# motor4.net
KiCad netlist of a schematic drawn in EAGLE
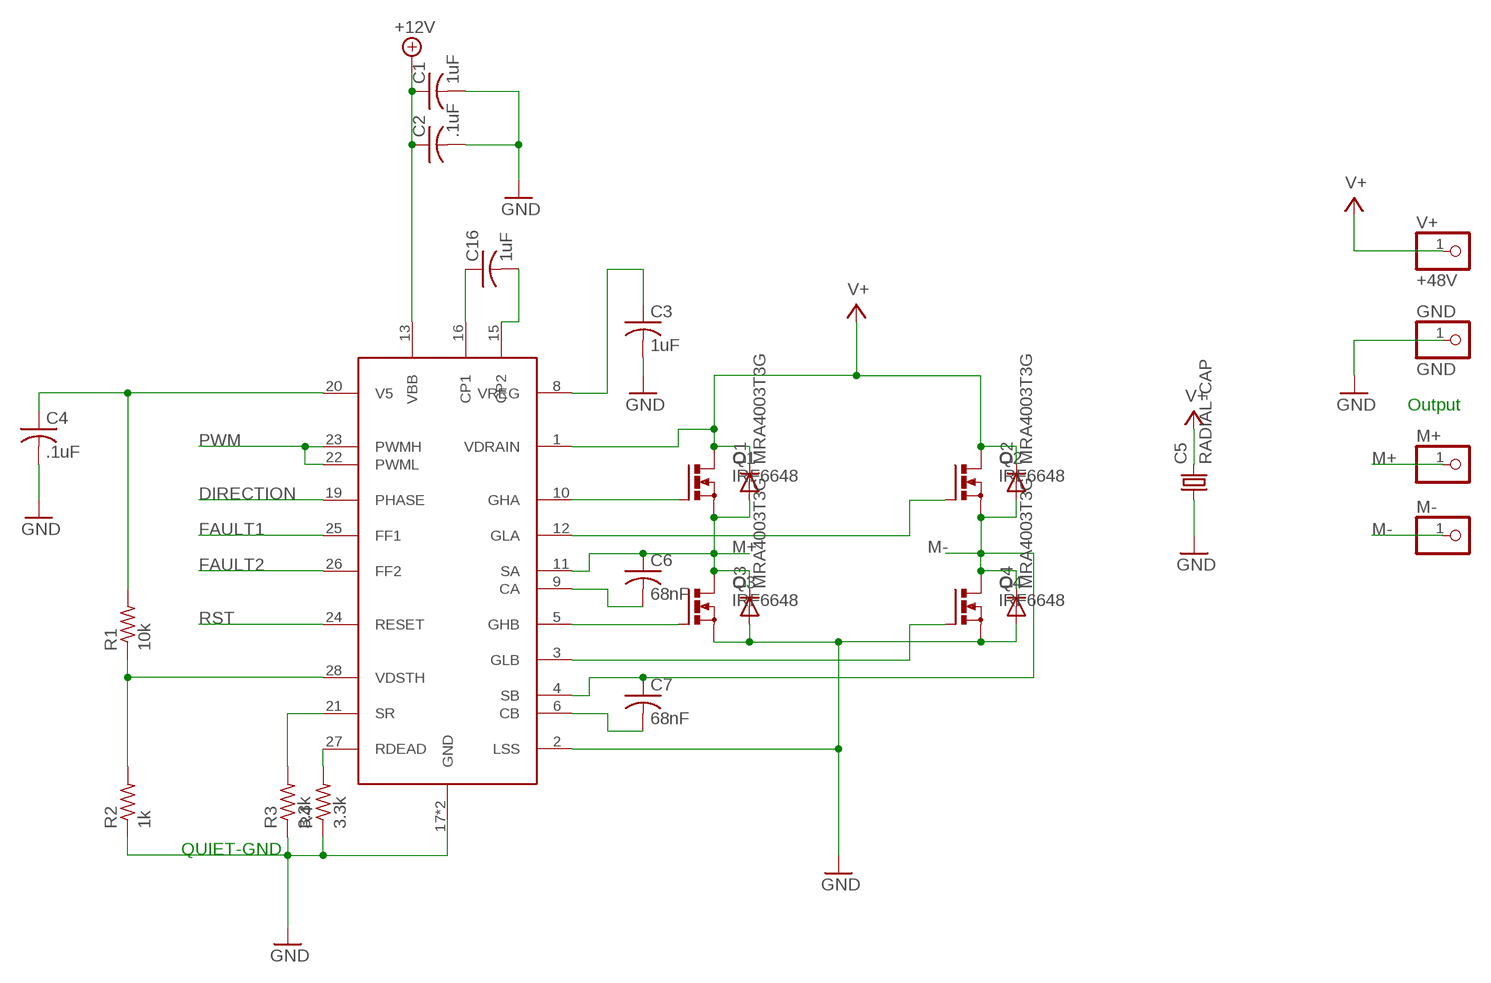
[diagram p0: schematic, sheet 1]
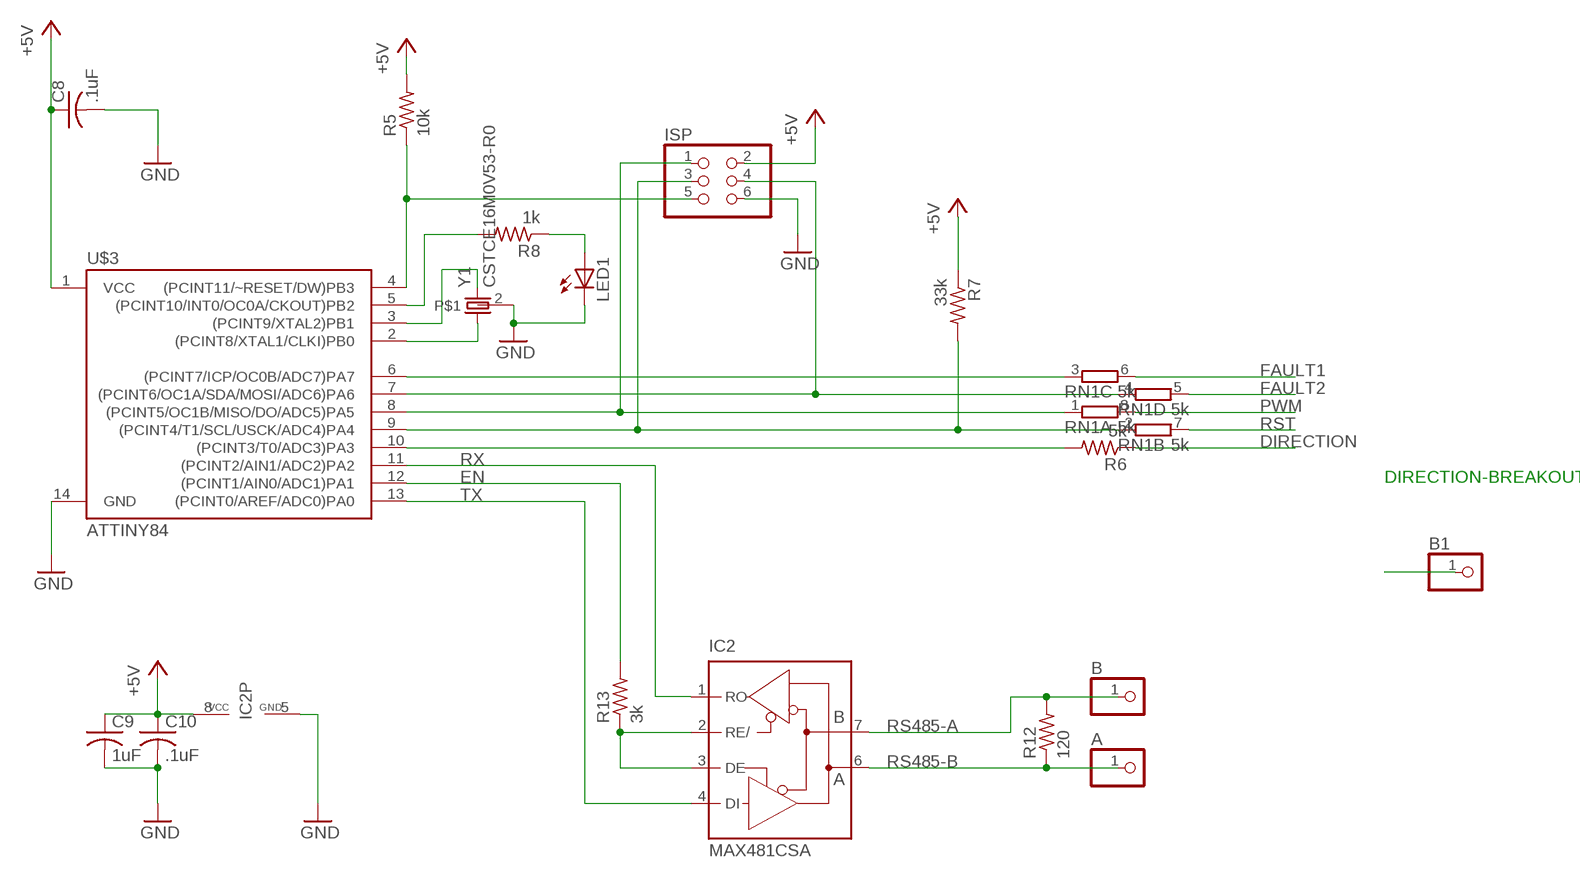
[diagram p1: schematic, sheet 2]
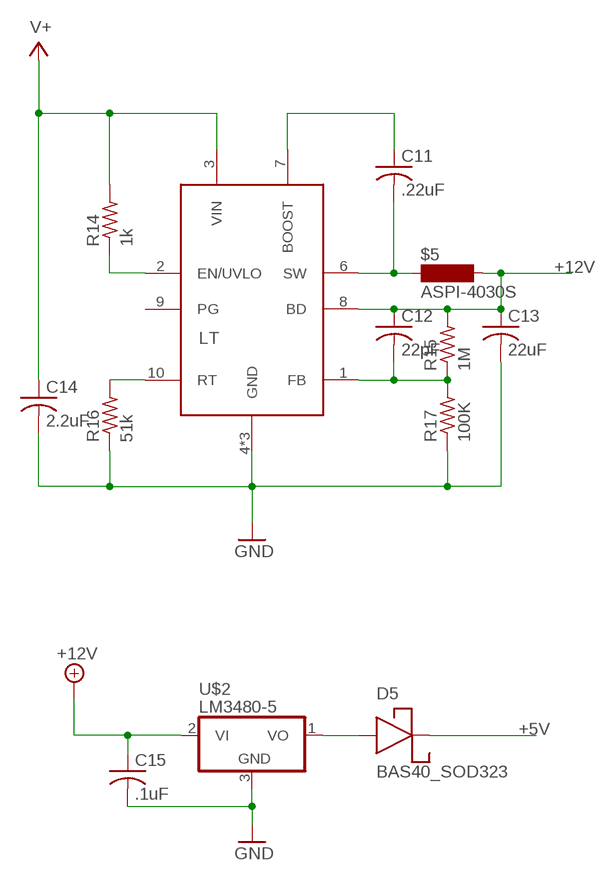
[diagram p2: schematic, sheet 3]

(export (version "E")
  (design (tool "Eeschema 10.0.6"))
  (components
    (comp (ref "$5")
      (value "ASPI-4030S")
      (footprint "eagle-import:ASPI-4030S")
      (libsource (lib "eagle-import") (part "ASPI-4030S"))
    )
    (comp (ref "C11")
      (value ".22uF")
      (footprint "eagle-import:C0603")
      (libsource (lib "eagle-import") (part "C-USC0603"))
    )
    (comp (ref "C12")
      (value "22pF")
      (footprint "eagle-import:C0603")
      (libsource (lib "eagle-import") (part "C-USC0603"))
    )
    (comp (ref "C13")
      (value "22uF")
      (footprint "eagle-import:C0805")
      (libsource (lib "eagle-import") (part "C-USC0805"))
    )
    (comp (ref "C14")
      (value "2.2uF")
      (footprint "eagle-import:C0603")
      (libsource (lib "eagle-import") (part "C-USC0603"))
    )
    (comp (ref "C15")
      (value ".1uF")
      (footprint "eagle-import:C0603")
      (libsource (lib "eagle-import") (part "C-USC0603"))
    )
    (comp (ref "D5")
      (value "BAS40_SOD323")
      (footprint "eagle-import:SOD323")
      (libsource (lib "eagle-import") (part "BAS40_SOD323"))
    )
    (comp (ref "LT")
      (value "LT3990")
      (footprint "eagle-import:DFN10-3X3")
      (libsource (lib "eagle-import") (part "LT3990"))
    )
    (comp (ref "R14")
      (value "1k")
      (footprint "eagle-import:R0603")
      (libsource (lib "eagle-import") (part "R-US_R0603"))
    )
    (comp (ref "R15")
      (value "1M")
      (footprint "eagle-import:R0603")
      (libsource (lib "eagle-import") (part "R-US_R0603"))
    )
    (comp (ref "R16")
      (value "51k")
      (footprint "eagle-import:R0603")
      (libsource (lib "eagle-import") (part "R-US_R0603"))
    )
    (comp (ref "R17")
      (value "100K")
      (footprint "eagle-import:R0603")
      (libsource (lib "eagle-import") (part "R-US_R0603"))
    )
    (comp (ref "U$2")
      (value "LM3480-5")
      (footprint "eagle-import:SOT23")
      (libsource (lib "eagle-import") (part "LM3480-5"))
    )
    (comp (ref "A")
      (value "PINHD-1X1")
      (footprint "eagle-import:1X01")
      (libsource (lib "eagle-import") (part "PINHD-1X1"))
    )
    (comp (ref "B")
      (value "PINHD-1X1")
      (footprint "eagle-import:1X01")
      (libsource (lib "eagle-import") (part "PINHD-1X1"))
    )
    (comp (ref "B1")
      (value "PINHD-1X1")
      (footprint "eagle-import:1X01")
      (libsource (lib "eagle-import") (part "PINHD-1X1"))
    )
    (comp (ref "C8")
      (value ".1uF")
      (footprint "eagle-import:C0603")
      (libsource (lib "eagle-import") (part "C-USC0603"))
    )
    (comp (ref "C9")
      (value "1uF")
      (footprint "eagle-import:C0603")
      (libsource (lib "eagle-import") (part "C-USC0603"))
    )
    (comp (ref "C10")
      (value ".1uF")
      (footprint "eagle-import:C0603")
      (libsource (lib "eagle-import") (part "C-USC0603"))
    )
    (comp (ref "IC2")
      (value "MAX481CSA")
      (footprint "eagle-import:SO08")
      (fields (field (name "MF") "MAXIM"))
      (libsource (lib "eagle-import") (part "MAX481CSA"))
    )
    (comp (ref "ISP")
      (value "PINHD-2X3")
      (footprint "eagle-import:2X03")
      (libsource (lib "eagle-import") (part "PINHD-2X3"))
    )
    (comp (ref "LED1")
      (value "LEDCHIPLED_0603")
      (footprint "eagle-import:CHIPLED_0603")
      (libsource (lib "eagle-import") (part "LEDCHIPLED_0603"))
    )
    (comp (ref "R5")
      (value "10k")
      (footprint "eagle-import:R0603")
      (libsource (lib "eagle-import") (part "R-US_R0603"))
    )
    (comp (ref "R6")
      (value "5k")
      (footprint "eagle-import:R0603")
      (libsource (lib "eagle-import") (part "R-US_R0603"))
    )
    (comp (ref "R7")
      (value "33k")
      (footprint "eagle-import:R0603")
      (libsource (lib "eagle-import") (part "R-US_R0603"))
    )
    (comp (ref "R8")
      (value "1k")
      (footprint "eagle-import:R0603")
      (libsource (lib "eagle-import") (part "R-US_R0603"))
    )
    (comp (ref "R12")
      (value "120")
      (footprint "eagle-import:R0603")
      (libsource (lib "eagle-import") (part "R-US_R0603"))
    )
    (comp (ref "R13")
      (value "3k")
      (footprint "eagle-import:R0603")
      (libsource (lib "eagle-import") (part "R-US_R0603"))
    )
    (comp (ref "RN1")
      (value "5k")
      (footprint "eagle-import:EXB38V")
      (libsource (lib "eagle-import") (part "4R-NEXB38V"))
    )
    (comp (ref "U$3")
      (value "ATTINY84")
      (footprint "eagle-import:SO14")
      (libsource (lib "eagle-import") (part "ATTINY84"))
    )
    (comp (ref "Y1")
      (value "CSTCE16M0V53-R0")
      (footprint "eagle-import:MYSMD2_RESONATOR")
      (libsource (lib "eagle-import") (part "CSTCE16M0V53-R0"))
    )
    (comp (ref "ALLGR")
      (value "ALLEGRO-A3921")
      (footprint "eagle-import:TSSOP28")
      (libsource (lib "eagle-import") (part "ALLEGRO-A3921"))
    )
    (comp (ref "C1")
      (value "1uF")
      (footprint "eagle-import:C0603")
      (libsource (lib "eagle-import") (part "C-USC0603"))
    )
    (comp (ref "C2")
      (value ".1uF")
      (footprint "eagle-import:C0603")
      (libsource (lib "eagle-import") (part "C-USC0603"))
    )
    (comp (ref "C3")
      (value "1uF")
      (footprint "eagle-import:C0603")
      (libsource (lib "eagle-import") (part "C-USC0603"))
    )
    (comp (ref "C4")
      (value ".1uF")
      (footprint "eagle-import:C0603")
      (libsource (lib "eagle-import") (part "C-USC0603"))
    )
    (comp (ref "C5")
      (value "RADIAL-CAP")
      (footprint "eagle-import:RADIAL-CAP")
      (libsource (lib "eagle-import") (part "RADIAL-CAP"))
    )
    (comp (ref "C6")
      (value "68nF")
      (footprint "eagle-import:C0603")
      (libsource (lib "eagle-import") (part "C-USC0603"))
    )
    (comp (ref "C7")
      (value "68nF")
      (footprint "eagle-import:C0603")
      (libsource (lib "eagle-import") (part "C-USC0603"))
    )
    (comp (ref "C16")
      (value "1uF")
      (footprint "eagle-import:C0603")
      (libsource (lib "eagle-import") (part "C-USC0603"))
    )
    (comp (ref "D1")
      (value "MRA4003T3G")
      (footprint "eagle-import:SMA")
      (libsource (lib "eagle-import") (part "MRA4003T3G"))
    )
    (comp (ref "D2")
      (value "MRA4003T3G")
      (footprint "eagle-import:SMA")
      (libsource (lib "eagle-import") (part "MRA4003T3G"))
    )
    (comp (ref "D3")
      (value "MRA4003T3G")
      (footprint "eagle-import:SMA")
      (libsource (lib "eagle-import") (part "MRA4003T3G"))
    )
    (comp (ref "D4")
      (value "MRA4003T3G")
      (footprint "eagle-import:SMA")
      (libsource (lib "eagle-import") (part "MRA4003T3G"))
    )
    (comp (ref "GND")
      (value "GND")
      (footprint "eagle-import:1X01")
      (libsource (lib "eagle-import") (part "PINHD-1X1"))
    )
    (comp (ref "M+")
      (value "PINHD-1X1")
      (footprint "eagle-import:1X01")
      (libsource (lib "eagle-import") (part "PINHD-1X1"))
    )
    (comp (ref "M-")
      (value "PINHD-1X1")
      (footprint "eagle-import:1X01")
      (libsource (lib "eagle-import") (part "PINHD-1X1"))
    )
    (comp (ref "Q1")
      (value "IRF6648")
      (footprint "eagle-import:DIRECTFET")
      (libsource (lib "eagle-import") (part "IRF6648"))
    )
    (comp (ref "Q2")
      (value "IRF6648")
      (footprint "eagle-import:DIRECTFET")
      (libsource (lib "eagle-import") (part "IRF6648"))
    )
    (comp (ref "Q3")
      (value "IRF6648")
      (footprint "eagle-import:DIRECTFET")
      (libsource (lib "eagle-import") (part "IRF6648"))
    )
    (comp (ref "Q4")
      (value "IRF6648")
      (footprint "eagle-import:DIRECTFET")
      (libsource (lib "eagle-import") (part "IRF6648"))
    )
    (comp (ref "R1")
      (value "10k")
      (footprint "eagle-import:R0603")
      (libsource (lib "eagle-import") (part "R-US_R0603"))
    )
    (comp (ref "R2")
      (value "1k")
      (footprint "eagle-import:R0603")
      (libsource (lib "eagle-import") (part "R-US_R0603"))
    )
    (comp (ref "R3")
      (value "3.3k")
      (footprint "eagle-import:R0603")
      (libsource (lib "eagle-import") (part "R-US_R0603"))
    )
    (comp (ref "R4")
      (value "3.3k")
      (footprint "eagle-import:R0603")
      (libsource (lib "eagle-import") (part "R-US_R0603"))
    )
    (comp (ref "V+")
      (value "+48V")
      (footprint "eagle-import:1X01")
      (libsource (lib "eagle-import") (part "PINHD-1X1"))
    )
  )
  (nets
    (net (code "1") (name "+5V") (class "Default")
      (node (ref "C10") (pin "1") (pinfunction "1_1") (pintype "passive"))
      (node (ref "C8") (pin "1") (pinfunction "1_1") (pintype "passive"))
      (node (ref "C9") (pin "1") (pinfunction "1_1") (pintype "passive"))
      (node (ref "D5") (pin "1") (pinfunction "P$2_1") (pintype "bidirectional"))
      (node (ref "IC2") (pin "8") (pinfunction "VCC_8") (pintype "power_in"))
      (node (ref "ISP") (pin "2") (pinfunction "2_2") (pintype "passive"))
      (node (ref "R5") (pin "2") (pinfunction "2_2") (pintype "passive"))
      (node (ref "R7") (pin "1") (pinfunction "1_1") (pintype "passive"))
      (node (ref "U$3") (pin "1") (pinfunction "VCC_1") (pintype "bidirectional"))
    )
    (net (code "2") (name "+12V") (class "Default")
      (node (ref "$5") (pin "P$2") (pinfunction "2_P$2") (pintype "passive"))
      (node (ref "ALLGR") (pin "13") (pinfunction "VBB_13") (pintype "bidirectional"))
      (node (ref "C1") (pin "1") (pinfunction "1_1") (pintype "passive"))
      (node (ref "C12") (pin "1") (pinfunction "1_1") (pintype "passive"))
      (node (ref "C13") (pin "1") (pinfunction "1_1") (pintype "passive"))
      (node (ref "C15") (pin "1") (pinfunction "1_1") (pintype "passive"))
      (node (ref "C2") (pin "1") (pinfunction "1_1") (pintype "passive"))
      (node (ref "LT") (pin "8") (pinfunction "BD_8") (pintype "bidirectional"))
      (node (ref "R15") (pin "2") (pinfunction "2_2") (pintype "passive"))
      (node (ref "U$2") (pin "2") (pinfunction "VI_2") (pintype "input"))
    )
    (net (code "3") (name "DIRECTION") (class "Default")
      (node (ref "ALLGR") (pin "19") (pinfunction "PHASE_19") (pintype "bidirectional"))
      (node (ref "R6") (pin "1") (pinfunction "1_1") (pintype "passive"))
    )
    (net (code "4") (name "EN") (class "Default")
      (node (ref "R13") (pin "2") (pinfunction "2_2") (pintype "passive"))
      (node (ref "U$3") (pin "12") (pinfunction "(PCINT1/AIN0/ADC1)PA1_12") (pintype "bidirectional"))
    )
    (net (code "5") (name "FAULT1") (class "Default")
      (node (ref "ALLGR") (pin "25") (pinfunction "FF1_25") (pintype "bidirectional"))
      (node (ref "RN1") (pin "6") (pinfunction "2_6") (pintype "passive"))
    )
    (net (code "6") (name "FAULT2") (class "Default")
      (node (ref "ALLGR") (pin "26") (pinfunction "FF2_26") (pintype "bidirectional"))
      (node (ref "RN1") (pin "5") (pinfunction "2_5") (pintype "passive"))
    )
    (net (code "7") (name "GND") (class "Default")
      (node (ref "ALLGR") (pin "17") (pinfunction "GND_17") (pintype "bidirectional"))
      (node (ref "ALLGR") (pin "2") (pinfunction "LSS_2") (pintype "bidirectional"))
      (node (ref "ALLGR") (pin "P$1") (pinfunction "GND_P$1") (pintype "bidirectional"))
      (node (ref "C1") (pin "2") (pinfunction "2_2") (pintype "passive"))
      (node (ref "C10") (pin "2") (pinfunction "2_2") (pintype "passive"))
      (node (ref "C13") (pin "2") (pinfunction "2_2") (pintype "passive"))
      (node (ref "C14") (pin "2") (pinfunction "2_2") (pintype "passive"))
      (node (ref "C15") (pin "2") (pinfunction "2_2") (pintype "passive"))
      (node (ref "C2") (pin "2") (pinfunction "2_2") (pintype "passive"))
      (node (ref "C3") (pin "2") (pinfunction "2_2") (pintype "passive"))
      (node (ref "C4") (pin "2") (pinfunction "2_2") (pintype "passive"))
      (node (ref "C5") (pin "P$2") (pinfunction "1_P$2") (pintype "passive"))
      (node (ref "C8") (pin "2") (pinfunction "2_2") (pintype "passive"))
      (node (ref "C9") (pin "2") (pinfunction "2_2") (pintype "passive"))
      (node (ref "D3") (pin "A") (pinfunction "A_A") (pintype "passive"))
      (node (ref "D4") (pin "A") (pinfunction "A_A") (pintype "passive"))
      (node (ref "GND") (pin "1") (pinfunction "1_1") (pintype "passive"))
      (node (ref "IC2") (pin "5") (pinfunction "GND_5") (pintype "power_in"))
      (node (ref "ISP") (pin "6") (pinfunction "6_6") (pintype "passive"))
      (node (ref "LED1") (pin "C") (pinfunction "C_C") (pintype "passive"))
      (node (ref "LT") (pin "4") (pinfunction "GND_4") (pintype "bidirectional"))
      (node (ref "LT") (pin "5") (pinfunction "GND_5") (pintype "bidirectional"))
      (node (ref "LT") (pin "EXP") (pinfunction "GND_EXP") (pintype "bidirectional"))
      (node (ref "Q3") (pin "S@1") (pinfunction "S_S@1") (pintype "passive"))
      (node (ref "Q3") (pin "S@2") (pinfunction "S_S@2") (pintype "passive"))
      (node (ref "Q4") (pin "S@1") (pinfunction "S_S@1") (pintype "passive"))
      (node (ref "Q4") (pin "S@2") (pinfunction "S_S@2") (pintype "passive"))
      (node (ref "R16") (pin "1") (pinfunction "1_1") (pintype "passive"))
      (node (ref "R17") (pin "1") (pinfunction "1_1") (pintype "passive"))
      (node (ref "R2") (pin "1") (pinfunction "1_1") (pintype "passive"))
      (node (ref "R3") (pin "1") (pinfunction "1_1") (pintype "passive"))
      (node (ref "R4") (pin "1") (pinfunction "1_1") (pintype "passive"))
      (node (ref "U$2") (pin "3") (pinfunction "GND_3") (pintype "input"))
      (node (ref "U$3") (pin "14") (pinfunction "GND_14") (pintype "bidirectional"))
      (node (ref "Y1") (pin "2") (pinfunction "P$1_2") (pintype "bidirectional"))
    )
    (net (code "8") (name "M+") (class "Default")
      (node (ref "ALLGR") (pin "11") (pinfunction "SA_11") (pintype "bidirectional"))
      (node (ref "C6") (pin "1") (pinfunction "1_1") (pintype "passive"))
      (node (ref "D1") (pin "A") (pinfunction "A_A") (pintype "passive"))
      (node (ref "D3") (pin "C") (pinfunction "C_C") (pintype "passive"))
      (node (ref "M+") (pin "1") (pinfunction "1_1") (pintype "passive"))
      (node (ref "Q1") (pin "S@1") (pinfunction "S_S@1") (pintype "passive"))
      (node (ref "Q1") (pin "S@2") (pinfunction "S_S@2") (pintype "passive"))
      (node (ref "Q3") (pin "D@1") (pinfunction "D_D@1") (pintype "passive"))
      (node (ref "Q3") (pin "D@2") (pinfunction "D_D@2") (pintype "passive"))
      (node (ref "Q3") (pin "D@3") (pinfunction "D_D@3") (pintype "passive"))
      (node (ref "Q3") (pin "D@4") (pinfunction "D_D@4") (pintype "passive"))
    )
    (net (code "9") (name "M-") (class "Default")
      (node (ref "ALLGR") (pin "4") (pinfunction "SB_4") (pintype "bidirectional"))
      (node (ref "C7") (pin "1") (pinfunction "1_1") (pintype "passive"))
      (node (ref "D2") (pin "A") (pinfunction "A_A") (pintype "passive"))
      (node (ref "D4") (pin "C") (pinfunction "C_C") (pintype "passive"))
      (node (ref "M-") (pin "1") (pinfunction "1_1") (pintype "passive"))
      (node (ref "Q2") (pin "S@1") (pinfunction "S_S@1") (pintype "passive"))
      (node (ref "Q2") (pin "S@2") (pinfunction "S_S@2") (pintype "passive"))
      (node (ref "Q4") (pin "D@1") (pinfunction "D_D@1") (pintype "passive"))
      (node (ref "Q4") (pin "D@2") (pinfunction "D_D@2") (pintype "passive"))
      (node (ref "Q4") (pin "D@3") (pinfunction "D_D@3") (pintype "passive"))
      (node (ref "Q4") (pin "D@4") (pinfunction "D_D@4") (pintype "passive"))
    )
    (net (code "10") (name "N$19") (class "Default")
      (node (ref "B1") (pin "1") (pinfunction "1_1") (pintype "passive"))
      (node (ref "R6") (pin "2") (pinfunction "2_2") (pintype "passive"))
      (node (ref "U$3") (pin "10") (pinfunction "(PCINT3/T0/ADC3)PA3_10") (pintype "bidirectional"))
    )
    (net (code "11") (name "Net-($5-1)") (class "Default")
      (node (ref "$5") (pin "P$1") (pinfunction "1_P$1") (pintype "passive"))
      (node (ref "C11") (pin "2") (pinfunction "2_2") (pintype "passive"))
      (node (ref "LT") (pin "6") (pinfunction "SW_6") (pintype "bidirectional"))
    )
    (net (code "12") (name "Net-(ALLGR-CA)") (class "Default")
      (node (ref "ALLGR") (pin "9") (pinfunction "CA_9") (pintype "bidirectional"))
      (node (ref "C6") (pin "2") (pinfunction "2_2") (pintype "passive"))
    )
    (net (code "13") (name "Net-(ALLGR-CB)") (class "Default")
      (node (ref "ALLGR") (pin "6") (pinfunction "CB_6") (pintype "bidirectional"))
      (node (ref "C7") (pin "2") (pinfunction "2_2") (pintype "passive"))
    )
    (net (code "14") (name "Net-(ALLGR-CP1)") (class "Default")
      (node (ref "ALLGR") (pin "16") (pinfunction "CP1_16") (pintype "bidirectional"))
      (node (ref "C16") (pin "1") (pinfunction "1_1") (pintype "passive"))
    )
    (net (code "15") (name "Net-(ALLGR-CP2)") (class "Default")
      (node (ref "ALLGR") (pin "15") (pinfunction "CP2_15") (pintype "bidirectional"))
      (node (ref "C16") (pin "2") (pinfunction "2_2") (pintype "passive"))
    )
    (net (code "16") (name "Net-(ALLGR-GHA)") (class "Default")
      (node (ref "ALLGR") (pin "10") (pinfunction "GHA_10") (pintype "bidirectional"))
      (node (ref "Q1") (pin "G") (pinfunction "G_G") (pintype "passive"))
    )
    (net (code "17") (name "Net-(ALLGR-GHB)") (class "Default")
      (node (ref "ALLGR") (pin "5") (pinfunction "GHB_5") (pintype "bidirectional"))
      (node (ref "Q3") (pin "G") (pinfunction "G_G") (pintype "passive"))
    )
    (net (code "18") (name "Net-(ALLGR-GLA)") (class "Default")
      (node (ref "ALLGR") (pin "12") (pinfunction "GLA_12") (pintype "bidirectional"))
      (node (ref "Q2") (pin "G") (pinfunction "G_G") (pintype "passive"))
    )
    (net (code "19") (name "Net-(ALLGR-GLB)") (class "Default")
      (node (ref "ALLGR") (pin "3") (pinfunction "GLB_3") (pintype "bidirectional"))
      (node (ref "Q4") (pin "G") (pinfunction "G_G") (pintype "passive"))
    )
    (net (code "20") (name "Net-(ALLGR-RDEAD)") (class "Default")
      (node (ref "ALLGR") (pin "27") (pinfunction "RDEAD_27") (pintype "bidirectional"))
      (node (ref "R4") (pin "2") (pinfunction "2_2") (pintype "passive"))
    )
    (net (code "21") (name "Net-(ALLGR-SR)") (class "Default")
      (node (ref "ALLGR") (pin "21") (pinfunction "SR_21") (pintype "bidirectional"))
      (node (ref "R3") (pin "2") (pinfunction "2_2") (pintype "passive"))
    )
    (net (code "22") (name "Net-(ALLGR-V5)") (class "Default")
      (node (ref "ALLGR") (pin "20") (pinfunction "V5_20") (pintype "bidirectional"))
      (node (ref "C4") (pin "1") (pinfunction "1_1") (pintype "passive"))
      (node (ref "R1") (pin "2") (pinfunction "2_2") (pintype "passive"))
    )
    (net (code "23") (name "Net-(ALLGR-VDSTH)") (class "Default")
      (node (ref "ALLGR") (pin "28") (pinfunction "VDSTH_28") (pintype "bidirectional"))
      (node (ref "R1") (pin "1") (pinfunction "1_1") (pintype "passive"))
      (node (ref "R2") (pin "2") (pinfunction "2_2") (pintype "passive"))
    )
    (net (code "24") (name "Net-(ALLGR-VREG)") (class "Default")
      (node (ref "ALLGR") (pin "8") (pinfunction "VREG_8") (pintype "bidirectional"))
      (node (ref "C3") (pin "1") (pinfunction "1_1") (pintype "passive"))
    )
    (net (code "25") (name "Net-(D5-P$1)") (class "Default")
      (node (ref "D5") (pin "2") (pinfunction "P$1_2") (pintype "bidirectional"))
      (node (ref "U$2") (pin "1") (pinfunction "VO_1") (pintype "passive"))
    )
    (net (code "26") (name "Net-(IC2A-DE)") (class "Default")
      (node (ref "IC2") (pin "2") (pinfunction "RE/_2") (pintype "input"))
      (node (ref "IC2") (pin "3") (pinfunction "DE_3") (pintype "input"))
      (node (ref "R13") (pin "1") (pinfunction "1_1") (pintype "passive"))
    )
    (net (code "27") (name "Net-(LED1-PadA)") (class "Default")
      (node (ref "LED1") (pin "A") (pinfunction "A_A") (pintype "passive"))
      (node (ref "R8") (pin "1") (pinfunction "1_1") (pintype "passive"))
    )
    (net (code "28") (name "Net-(LT-BOOST)") (class "Default")
      (node (ref "C11") (pin "1") (pinfunction "1_1") (pintype "passive"))
      (node (ref "LT") (pin "7") (pinfunction "BOOST_7") (pintype "bidirectional"))
    )
    (net (code "29") (name "Net-(LT-EN{slash}UVLO)") (class "Default")
      (node (ref "LT") (pin "2") (pinfunction "EN/UVLO_2") (pintype "bidirectional"))
      (node (ref "R14") (pin "1") (pinfunction "1_1") (pintype "passive"))
    )
    (net (code "30") (name "Net-(LT-FB)") (class "Default")
      (node (ref "C12") (pin "2") (pinfunction "2_2") (pintype "passive"))
      (node (ref "LT") (pin "1") (pinfunction "FB_1") (pintype "bidirectional"))
      (node (ref "R15") (pin "1") (pinfunction "1_1") (pintype "passive"))
      (node (ref "R17") (pin "2") (pinfunction "2_2") (pintype "passive"))
    )
    (net (code "31") (name "Net-(LT-RT)") (class "Default")
      (node (ref "LT") (pin "10") (pinfunction "RT_10") (pintype "bidirectional"))
      (node (ref "R16") (pin "2") (pinfunction "2_2") (pintype "passive"))
    )
    (net (code "32") (name "Net-(RN1B-1)") (class "Default")
      (node (ref "ISP") (pin "3") (pinfunction "3_3") (pintype "passive"))
      (node (ref "R7") (pin "2") (pinfunction "2_2") (pintype "passive"))
      (node (ref "RN1") (pin "2") (pinfunction "1_2") (pintype "passive"))
      (node (ref "U$3") (pin "9") (pinfunction "(PCINT4/T1/SCL/USCK/ADC4)PA4_9") (pintype "bidirectional"))
    )
    (net (code "33") (name "Net-(RN1C-1)") (class "Default")
      (node (ref "RN1") (pin "3") (pinfunction "1_3") (pintype "passive"))
      (node (ref "U$3") (pin "6") (pinfunction "(PCINT7/ICP/OC0B/ADC7)PA7_6") (pintype "bidirectional"))
    )
    (net (code "34") (name "Net-(RN1D-1)") (class "Default")
      (node (ref "ISP") (pin "4") (pinfunction "4_4") (pintype "passive"))
      (node (ref "RN1") (pin "4") (pinfunction "1_4") (pintype "passive"))
      (node (ref "U$3") (pin "7") (pinfunction "(PCINT6/OC1A/SDA/MOSI/ADC6)PA6_7") (pintype "bidirectional"))
    )
    (net (code "35") (name "Net-(U$3-(PCINT5{slash}OC1B{slash}MISO{slash}DO{slash}ADC5)PA5)") (class "Default")
      (node (ref "ISP") (pin "1") (pinfunction "1_1") (pintype "passive"))
      (node (ref "RN1") (pin "1") (pinfunction "1_1") (pintype "passive"))
      (node (ref "U$3") (pin "8") (pinfunction "(PCINT5/OC1B/MISO/DO/ADC5)PA5_8") (pintype "bidirectional"))
    )
    (net (code "36") (name "Net-(U$3-(PCINT8{slash}XTAL1{slash}CLKI)PB0)") (class "Default")
      (node (ref "U$3") (pin "2") (pinfunction "(PCINT8/XTAL1/CLKI)PB0_2") (pintype "bidirectional"))
      (node (ref "Y1") (pin "1") (pinfunction "1_1") (pintype "passive"))
    )
    (net (code "37") (name "Net-(U$3-(PCINT9{slash}XTAL2)PB1)") (class "Default")
      (node (ref "U$3") (pin "3") (pinfunction "(PCINT9/XTAL2)PB1_3") (pintype "bidirectional"))
      (node (ref "Y1") (pin "3") (pinfunction "2_3") (pintype "passive"))
    )
    (net (code "38") (name "Net-(U$3-(PCINT10{slash}INT0{slash}OC0A{slash}CKOUT)PB2)") (class "Default")
      (node (ref "R8") (pin "2") (pinfunction "2_2") (pintype "passive"))
      (node (ref "U$3") (pin "5") (pinfunction "(PCINT10/INT0/OC0A/CKOUT)PB2_5") (pintype "bidirectional"))
    )
    (net (code "39") (name "Net-(U$3-(PCINT11{slash}~{RESET{slash}DW})PB3)") (class "Default")
      (node (ref "ISP") (pin "5") (pinfunction "5_5") (pintype "passive"))
      (node (ref "R5") (pin "1") (pinfunction "1_1") (pintype "passive"))
      (node (ref "U$3") (pin "4") (pinfunction "(PCINT11/~{RESET/DW})PB3_4") (pintype "bidirectional"))
    )
    (net (code "40") (name "PWM") (class "Default")
      (node (ref "ALLGR") (pin "22") (pinfunction "PWML_22") (pintype "bidirectional"))
      (node (ref "ALLGR") (pin "23") (pinfunction "PWMH_23") (pintype "bidirectional"))
      (node (ref "RN1") (pin "8") (pinfunction "2_8") (pintype "passive"))
    )
    (net (code "41") (name "RS485-A") (class "Default")
      (node (ref "B") (pin "1") (pinfunction "1_1") (pintype "passive"))
      (node (ref "IC2") (pin "7") (pinfunction "B_7") (pintype "passive"))
      (node (ref "R12") (pin "2") (pinfunction "2_2") (pintype "passive"))
    )
    (net (code "42") (name "RS485-B") (class "Default")
      (node (ref "A") (pin "1") (pinfunction "1_1") (pintype "passive"))
      (node (ref "IC2") (pin "6") (pinfunction "A_6") (pintype "passive"))
      (node (ref "R12") (pin "1") (pinfunction "1_1") (pintype "passive"))
    )
    (net (code "43") (name "RST") (class "Default")
      (node (ref "ALLGR") (pin "24") (pinfunction "RESET_24") (pintype "bidirectional"))
      (node (ref "RN1") (pin "7") (pinfunction "2_7") (pintype "passive"))
    )
    (net (code "44") (name "RX") (class "Default")
      (node (ref "IC2") (pin "1") (pinfunction "RO_1") (pintype "output"))
      (node (ref "U$3") (pin "11") (pinfunction "(PCINT2/AIN1/ADC2)PA2_11") (pintype "bidirectional"))
    )
    (net (code "45") (name "TX") (class "Default")
      (node (ref "IC2") (pin "4") (pinfunction "DI_4") (pintype "input"))
      (node (ref "U$3") (pin "13") (pinfunction "(PCINT0/AREF/ADC0)PA0_13") (pintype "bidirectional"))
    )
    (net (code "46") (name "V+") (class "Default")
      (node (ref "ALLGR") (pin "1") (pinfunction "VDRAIN_1") (pintype "bidirectional"))
      (node (ref "C14") (pin "1") (pinfunction "1_1") (pintype "passive"))
      (node (ref "C5") (pin "P$1") (pinfunction "2_P$1") (pintype "passive"))
      (node (ref "D1") (pin "C") (pinfunction "C_C") (pintype "passive"))
      (node (ref "D2") (pin "C") (pinfunction "C_C") (pintype "passive"))
      (node (ref "LT") (pin "3") (pinfunction "VIN_3") (pintype "bidirectional"))
      (node (ref "Q1") (pin "D@1") (pinfunction "D_D@1") (pintype "passive"))
      (node (ref "Q1") (pin "D@2") (pinfunction "D_D@2") (pintype "passive"))
      (node (ref "Q1") (pin "D@3") (pinfunction "D_D@3") (pintype "passive"))
      (node (ref "Q1") (pin "D@4") (pinfunction "D_D@4") (pintype "passive"))
      (node (ref "Q2") (pin "D@1") (pinfunction "D_D@1") (pintype "passive"))
      (node (ref "Q2") (pin "D@2") (pinfunction "D_D@2") (pintype "passive"))
      (node (ref "Q2") (pin "D@3") (pinfunction "D_D@3") (pintype "passive"))
      (node (ref "Q2") (pin "D@4") (pinfunction "D_D@4") (pintype "passive"))
      (node (ref "R14") (pin "2") (pinfunction "2_2") (pintype "passive"))
      (node (ref "V+") (pin "1") (pinfunction "1_1") (pintype "passive"))
    )
    (net (code "47") (name "unconnected-(LT-PG-Pad9)") (class "Default")
      (node (ref "LT") (pin "9") (pinfunction "PG_9") (pintype "bidirectional"))
    )
  )
)
